# freezeTimeManualRoute.net
KiCad netlist of a schematic drawn in EAGLE
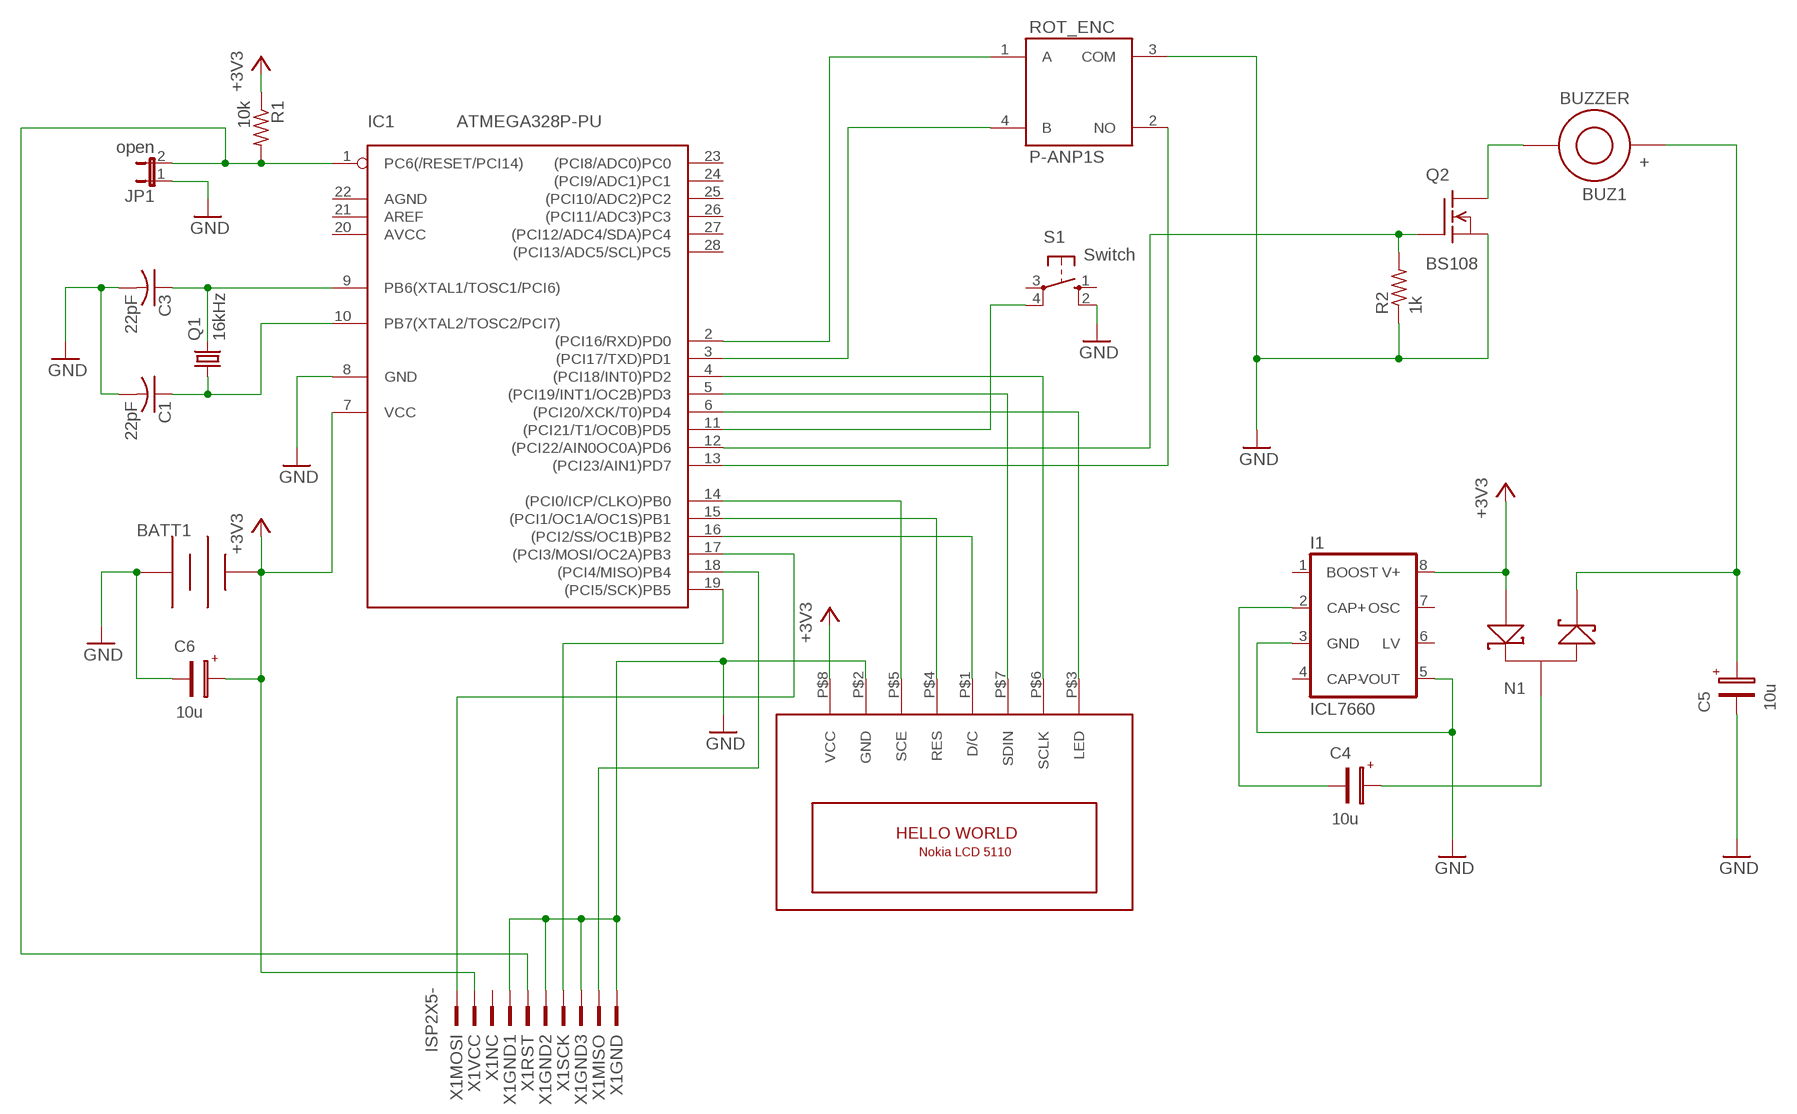
[diagram p0: schematic, sheet 1]

(export (version "E")
  (design (tool "Eeschema 10.0.6"))
  (components
    (comp (ref "BATT1")
      (value "3VBATTERY")
      (footprint "eagle-import:BH241-3A")
      (libsource (lib "eagle-import") (part "3VBATTERY"))
    )
    (comp (ref "BUZ1")
      (value "BUZZER")
      (footprint "eagle-import:AL1210MTE-P5R")
      (libsource (lib "eagle-import") (part "BUZZER"))
    )
    (comp (ref "C1")
      (value "22pF")
      (footprint "eagle-import:C1206")
      (libsource (lib "eagle-import") (part "C-USC1206"))
    )
    (comp (ref "C3")
      (value "22pF")
      (footprint "eagle-import:C1206")
      (libsource (lib "eagle-import") (part "C-USC1206"))
    )
    (comp (ref "C4")
      (value "10u")
      (footprint "eagle-import:C_6032-28R")
      (libsource (lib "eagle-import") (part "C-TANCTS"))
    )
    (comp (ref "C5")
      (value "10u")
      (footprint "eagle-import:C_6032-28R")
      (libsource (lib "eagle-import") (part "C-TANCTS"))
    )
    (comp (ref "C6")
      (value "10u")
      (footprint "eagle-import:C_6032-28R")
      (libsource (lib "eagle-import") (part "C-TANCTS"))
    )
    (comp (ref "I1")
      (value "ICL7660")
      (footprint "eagle-import:SO08")
      (libsource (lib "eagle-import") (part "ICL7660S7660SCBA"))
    )
    (comp (ref "IC1")
      (value "ATMEGA328P-PU")
      (footprint "eagle-import:DIL28-3")
      (libsource (lib "eagle-import") (part "ATMEGA168PV-10"))
    )
    (comp (ref "JP1")
      (value "open")
      (footprint "eagle-import:JP1")
      (libsource (lib "eagle-import") (part "JP1E"))
    )
    (comp (ref "LCD1")
      (value "LCD_NOKIA5110")
      (footprint "eagle-import:LCM5110_W")
      (libsource (lib "eagle-import") (part "LCD_NOKIA5110"))
    )
    (comp (ref "N1")
      (value "BAT54S")
      (footprint "eagle-import:SOT23")
      (libsource (lib "eagle-import") (part "BAT54SBAT54S"))
    )
    (comp (ref "Q1")
      (value "16kHz")
      (footprint "eagle-import:HC49U70")
      (libsource (lib "eagle-import") (part "CRYSTALHC49U70"))
    )
    (comp (ref "Q2")
      (value "BS108")
      (footprint "eagle-import:TO92-INLINE")
      (libsource (lib "eagle-import") (part "FQN1N50CI"))
    )
    (comp (ref "R1")
      (value "10k")
      (footprint "eagle-import:R1206")
      (libsource (lib "eagle-import") (part "R-US_R1206"))
    )
    (comp (ref "R2")
      (value "1k")
      (footprint "eagle-import:R1206")
      (libsource (lib "eagle-import") (part "R-US_R1206"))
    )
    (comp (ref "ROT_ENC")
      (value "P-ANP1S")
      (footprint "eagle-import:P-ANP1S")
      (libsource (lib "eagle-import") (part "P-ANP1SP-ANP1S"))
    )
    (comp (ref "S1")
      (value "Switch")
      (footprint "eagle-import:TACTS-24N")
      (fields (field (name "MF") "NINIGI"))
      (libsource (lib "eagle-import") (part "SPST_SWITCH"))
    )
    (comp (ref "X1")
      (value "ISP2X5-")
      (footprint "eagle-import:PAK100_2500-10")
      (fields (field (name "MF") "3M") (field (name "MPN") "2510-6002UB"))
      (libsource (lib "eagle-import") (part "ISP2X5-"))
    )
  )
  (nets
    (net (code "1") (name "+3V3") (class "Default")
      (node (ref "BATT1") (pin "+") (pinfunction "+_+") (pintype "bidirectional"))
      (node (ref "C6") (pin "+") (pinfunction "P$1_+") (pintype "passive"))
      (node (ref "I1") (pin "8") (pinfunction "V+_8") (pintype "power_in"))
      (node (ref "IC1") (pin "7") (pinfunction "VCC_7") (pintype "bidirectional"))
      (node (ref "LCD1") (pin "P$8") (pinfunction "VCC_P$8") (pintype "power_in"))
      (node (ref "N1") (pin "1") (pinfunction "P$2_1") (pintype "passive"))
      (node (ref "R1") (pin "1") (pinfunction "1_1") (pintype "passive"))
      (node (ref "X1") (pin "2") (pinfunction "KL_2") (pintype "passive"))
    )
    (net (code "2") (name "GND") (class "Default")
      (node (ref "BATT1") (pin "-") (pinfunction "-_-") (pintype "bidirectional"))
      (node (ref "C1") (pin "2") (pinfunction "2_2") (pintype "passive"))
      (node (ref "C3") (pin "2") (pinfunction "2_2") (pintype "passive"))
      (node (ref "C5") (pin "-") (pinfunction "P$2_-") (pintype "passive"))
      (node (ref "C6") (pin "-") (pinfunction "P$2_-") (pintype "passive"))
      (node (ref "I1") (pin "3") (pinfunction "GND_3") (pintype "power_in"))
      (node (ref "I1") (pin "5") (pinfunction "VOUT_5") (pintype "bidirectional"))
      (node (ref "IC1") (pin "8") (pinfunction "GND_8") (pintype "bidirectional"))
      (node (ref "JP1") (pin "1") (pinfunction "1_1") (pintype "passive"))
      (node (ref "LCD1") (pin "P$2") (pinfunction "GND_P$2") (pintype "power_in"))
      (node (ref "Q2") (pin "3") (pinfunction "S_3") (pintype "passive"))
      (node (ref "R2") (pin "1") (pinfunction "1_1") (pintype "passive"))
      (node (ref "ROT_ENC") (pin "3") (pinfunction "COM_3") (pintype "bidirectional"))
      (node (ref "S1") (pin "2") (pinfunction "S1_2") (pintype "passive"))
      (node (ref "X1") (pin "10") (pinfunction "KL_10") (pintype "passive"))
      (node (ref "X1") (pin "4") (pinfunction "KL_4") (pintype "passive"))
      (node (ref "X1") (pin "6") (pinfunction "KL_6") (pintype "passive"))
      (node (ref "X1") (pin "8") (pinfunction "KL_8") (pintype "passive"))
    )
    (net (code "3") (name "Net-(BUZ1-+)") (class "Default")
      (node (ref "BUZ1") (pin "1") (pinfunction "+_1") (pintype "bidirectional"))
      (node (ref "C5") (pin "+") (pinfunction "P$1_+") (pintype "passive"))
      (node (ref "N1") (pin "2") (pinfunction "P$3_2") (pintype "passive"))
    )
    (net (code "4") (name "Net-(BUZ1-P$2)") (class "Default")
      (node (ref "BUZ1") (pin "2") (pinfunction "P$2_2") (pintype "bidirectional"))
      (node (ref "Q2") (pin "1") (pinfunction "D_1") (pintype "passive"))
    )
    (net (code "5") (name "Net-(C4-P$1)") (class "Default")
      (node (ref "C4") (pin "+") (pinfunction "P$1_+") (pintype "passive"))
      (node (ref "N1") (pin "3") (pinfunction "P$1_3") (pintype "passive"))
    )
    (net (code "6") (name "Net-(C4-P$2)") (class "Default")
      (node (ref "C4") (pin "-") (pinfunction "P$2_-") (pintype "passive"))
      (node (ref "I1") (pin "2") (pinfunction "CAP+_2") (pintype "bidirectional"))
    )
    (net (code "7") (name "Net-(IC1-(PCI0{slash}ICP{slash}CLKO)PB0)") (class "Default")
      (node (ref "IC1") (pin "14") (pinfunction "(PCI0/ICP/CLKO)PB0_14") (pintype "bidirectional"))
      (node (ref "LCD1") (pin "P$5") (pinfunction "SCE_P$5") (pintype "bidirectional"))
    )
    (net (code "8") (name "Net-(IC1-(PCI1{slash}OC1A{slash}OC1S)PB1)") (class "Default")
      (node (ref "IC1") (pin "15") (pinfunction "(PCI1/OC1A/OC1S)PB1_15") (pintype "bidirectional"))
      (node (ref "LCD1") (pin "P$4") (pinfunction "RES_P$4") (pintype "bidirectional"))
    )
    (net (code "9") (name "Net-(IC1-(PCI2{slash}SS{slash}OC1B)PB2)") (class "Default")
      (node (ref "IC1") (pin "16") (pinfunction "(PCI2/SS/OC1B)PB2_16") (pintype "bidirectional"))
      (node (ref "LCD1") (pin "P$1") (pinfunction "D/C_P$1") (pintype "bidirectional"))
    )
    (net (code "10") (name "Net-(IC1-(PCI3{slash}MOSI{slash}OC2A)PB3)") (class "Default")
      (node (ref "IC1") (pin "17") (pinfunction "(PCI3/MOSI/OC2A)PB3_17") (pintype "bidirectional"))
      (node (ref "X1") (pin "1") (pinfunction "KL_1") (pintype "passive"))
    )
    (net (code "11") (name "Net-(IC1-(PCI4{slash}MISO)PB4)") (class "Default")
      (node (ref "IC1") (pin "18") (pinfunction "(PCI4/MISO)PB4_18") (pintype "bidirectional"))
      (node (ref "X1") (pin "9") (pinfunction "KL_9") (pintype "passive"))
    )
    (net (code "12") (name "Net-(IC1-(PCI5{slash}SCK)PB5)") (class "Default")
      (node (ref "IC1") (pin "19") (pinfunction "(PCI5/SCK)PB5_19") (pintype "bidirectional"))
      (node (ref "X1") (pin "7") (pinfunction "KL_7") (pintype "passive"))
    )
    (net (code "13") (name "Net-(IC1-(PCI16{slash}RXD)PD0)") (class "Default")
      (node (ref "IC1") (pin "2") (pinfunction "(PCI16/RXD)PD0_2") (pintype "bidirectional"))
      (node (ref "ROT_ENC") (pin "1") (pinfunction "A_1") (pintype "bidirectional"))
    )
    (net (code "14") (name "Net-(IC1-(PCI17{slash}TXD)PD1)") (class "Default")
      (node (ref "IC1") (pin "3") (pinfunction "(PCI17/TXD)PD1_3") (pintype "bidirectional"))
      (node (ref "ROT_ENC") (pin "4") (pinfunction "B_4") (pintype "bidirectional"))
    )
    (net (code "15") (name "Net-(IC1-(PCI18{slash}INT0)PD2)") (class "Default")
      (node (ref "IC1") (pin "4") (pinfunction "(PCI18/INT0)PD2_4") (pintype "bidirectional"))
      (node (ref "LCD1") (pin "P$6") (pinfunction "SCLK_P$6") (pintype "bidirectional"))
    )
    (net (code "16") (name "Net-(IC1-(PCI19{slash}INT1{slash}OC2B)PD3)") (class "Default")
      (node (ref "IC1") (pin "5") (pinfunction "(PCI19/INT1/OC2B)PD3_5") (pintype "bidirectional"))
      (node (ref "LCD1") (pin "P$7") (pinfunction "SDIN_P$7") (pintype "bidirectional"))
    )
    (net (code "17") (name "Net-(IC1-(PCI20{slash}XCK{slash}T0)PD4)") (class "Default")
      (node (ref "IC1") (pin "6") (pinfunction "(PCI20/XCK/T0)PD4_6") (pintype "bidirectional"))
      (node (ref "LCD1") (pin "P$3") (pinfunction "LED_P$3") (pintype "bidirectional"))
    )
    (net (code "18") (name "Net-(IC1-(PCI21{slash}T1{slash}OC0B)PD5)") (class "Default")
      (node (ref "IC1") (pin "11") (pinfunction "(PCI21/T1/OC0B)PD5_11") (pintype "bidirectional"))
      (node (ref "S1") (pin "4") (pinfunction "P1_4") (pintype "passive"))
    )
    (net (code "19") (name "Net-(IC1-(PCI22{slash}AIN0OC0A)PD6)") (class "Default")
      (node (ref "IC1") (pin "12") (pinfunction "(PCI22/AIN0OC0A)PD6_12") (pintype "bidirectional"))
      (node (ref "Q2") (pin "2") (pinfunction "G_2") (pintype "passive"))
      (node (ref "R2") (pin "2") (pinfunction "2_2") (pintype "passive"))
    )
    (net (code "20") (name "Net-(IC1-(PCI23{slash}AIN1)PD7)") (class "Default")
      (node (ref "IC1") (pin "13") (pinfunction "(PCI23/AIN1)PD7_13") (pintype "bidirectional"))
      (node (ref "ROT_ENC") (pin "2") (pinfunction "NO_2") (pintype "bidirectional"))
    )
    (net (code "21") (name "Net-(IC1-PB6(XTAL1{slash}TOSC1{slash}PCI6))") (class "Default")
      (node (ref "C3") (pin "1") (pinfunction "1_1") (pintype "passive"))
      (node (ref "IC1") (pin "9") (pinfunction "PB6(XTAL1/TOSC1/PCI6)_9") (pintype "bidirectional"))
      (node (ref "Q1") (pin "2") (pinfunction "2_2") (pintype "passive"))
    )
    (net (code "22") (name "Net-(IC1-PB7(XTAL2{slash}TOSC2{slash}PCI7))") (class "Default")
      (node (ref "C1") (pin "1") (pinfunction "1_1") (pintype "passive"))
      (node (ref "IC1") (pin "10") (pinfunction "PB7(XTAL2/TOSC2/PCI7)_10") (pintype "bidirectional"))
      (node (ref "Q1") (pin "1") (pinfunction "1_1") (pintype "passive"))
    )
    (net (code "23") (name "Net-(IC1-PC6({slash}RESET{slash}PCI14))") (class "Default")
      (node (ref "IC1") (pin "1") (pinfunction "PC6(/RESET/PCI14)_1") (pintype "bidirectional"))
      (node (ref "JP1") (pin "2") (pinfunction "2_2") (pintype "passive"))
      (node (ref "R1") (pin "2") (pinfunction "2_2") (pintype "passive"))
      (node (ref "X1") (pin "5") (pinfunction "KL_5") (pintype "passive"))
    )
    (net (code "24") (name "unconnected-(I1-BOOST-Pad1)") (class "Default")
      (node (ref "I1") (pin "1") (pinfunction "BOOST_1") (pintype "bidirectional"))
    )
    (net (code "25") (name "unconnected-(I1-CAP--Pad4)") (class "Default")
      (node (ref "I1") (pin "4") (pinfunction "CAP-_4") (pintype "bidirectional"))
    )
    (net (code "26") (name "unconnected-(I1-LV-Pad6)") (class "Default")
      (node (ref "I1") (pin "6") (pinfunction "LV_6") (pintype "bidirectional"))
    )
    (net (code "27") (name "unconnected-(I1-OSC-Pad7)") (class "Default")
      (node (ref "I1") (pin "7") (pinfunction "OSC_7") (pintype "bidirectional"))
    )
    (net (code "28") (name "unconnected-(IC1-(PCI8{slash}ADC0)PC0-Pad23)") (class "Default")
      (node (ref "IC1") (pin "23") (pinfunction "(PCI8/ADC0)PC0_23") (pintype "bidirectional"))
    )
    (net (code "29") (name "unconnected-(IC1-(PCI9{slash}ADC1)PC1-Pad24)") (class "Default")
      (node (ref "IC1") (pin "24") (pinfunction "(PCI9/ADC1)PC1_24") (pintype "bidirectional"))
    )
    (net (code "30") (name "unconnected-(IC1-(PCI10{slash}ADC2)PC2-Pad25)") (class "Default")
      (node (ref "IC1") (pin "25") (pinfunction "(PCI10/ADC2)PC2_25") (pintype "bidirectional"))
    )
    (net (code "31") (name "unconnected-(IC1-(PCI11{slash}ADC3)PC3-Pad26)") (class "Default")
      (node (ref "IC1") (pin "26") (pinfunction "(PCI11/ADC3)PC3_26") (pintype "bidirectional"))
    )
    (net (code "32") (name "unconnected-(IC1-(PCI12{slash}ADC4{slash}SDA)PC4-Pad27)") (class "Default")
      (node (ref "IC1") (pin "27") (pinfunction "(PCI12/ADC4/SDA)PC4_27") (pintype "bidirectional"))
    )
    (net (code "33") (name "unconnected-(IC1-(PCI13{slash}ADC5{slash}SCL)PC5-Pad28)") (class "Default")
      (node (ref "IC1") (pin "28") (pinfunction "(PCI13/ADC5/SCL)PC5_28") (pintype "bidirectional"))
    )
    (net (code "34") (name "unconnected-(IC1-AGND-Pad22)") (class "Default")
      (node (ref "IC1") (pin "22") (pinfunction "AGND_22") (pintype "bidirectional"))
    )
    (net (code "35") (name "unconnected-(IC1-AREF-Pad21)") (class "Default")
      (node (ref "IC1") (pin "21") (pinfunction "AREF_21") (pintype "bidirectional"))
    )
    (net (code "36") (name "unconnected-(IC1-AVCC-Pad20)") (class "Default")
      (node (ref "IC1") (pin "20") (pinfunction "AVCC_20") (pintype "bidirectional"))
    )
    (net (code "37") (name "unconnected-(S1-P-Pad3)") (class "Default")
      (node (ref "S1") (pin "3") (pinfunction "P_3") (pintype "passive"))
    )
    (net (code "38") (name "unconnected-(S1-S-Pad1)") (class "Default")
      (node (ref "S1") (pin "1") (pinfunction "S_1") (pintype "passive"))
    )
    (net (code "39") (name "unconnected-(X1G-KL-Pad3)") (class "Default")
      (node (ref "X1") (pin "3") (pinfunction "KL_3") (pintype "passive"))
    )
  )
)
